# Sheet1.net
KiCad netlist of a schematic drawn in Altium Designer
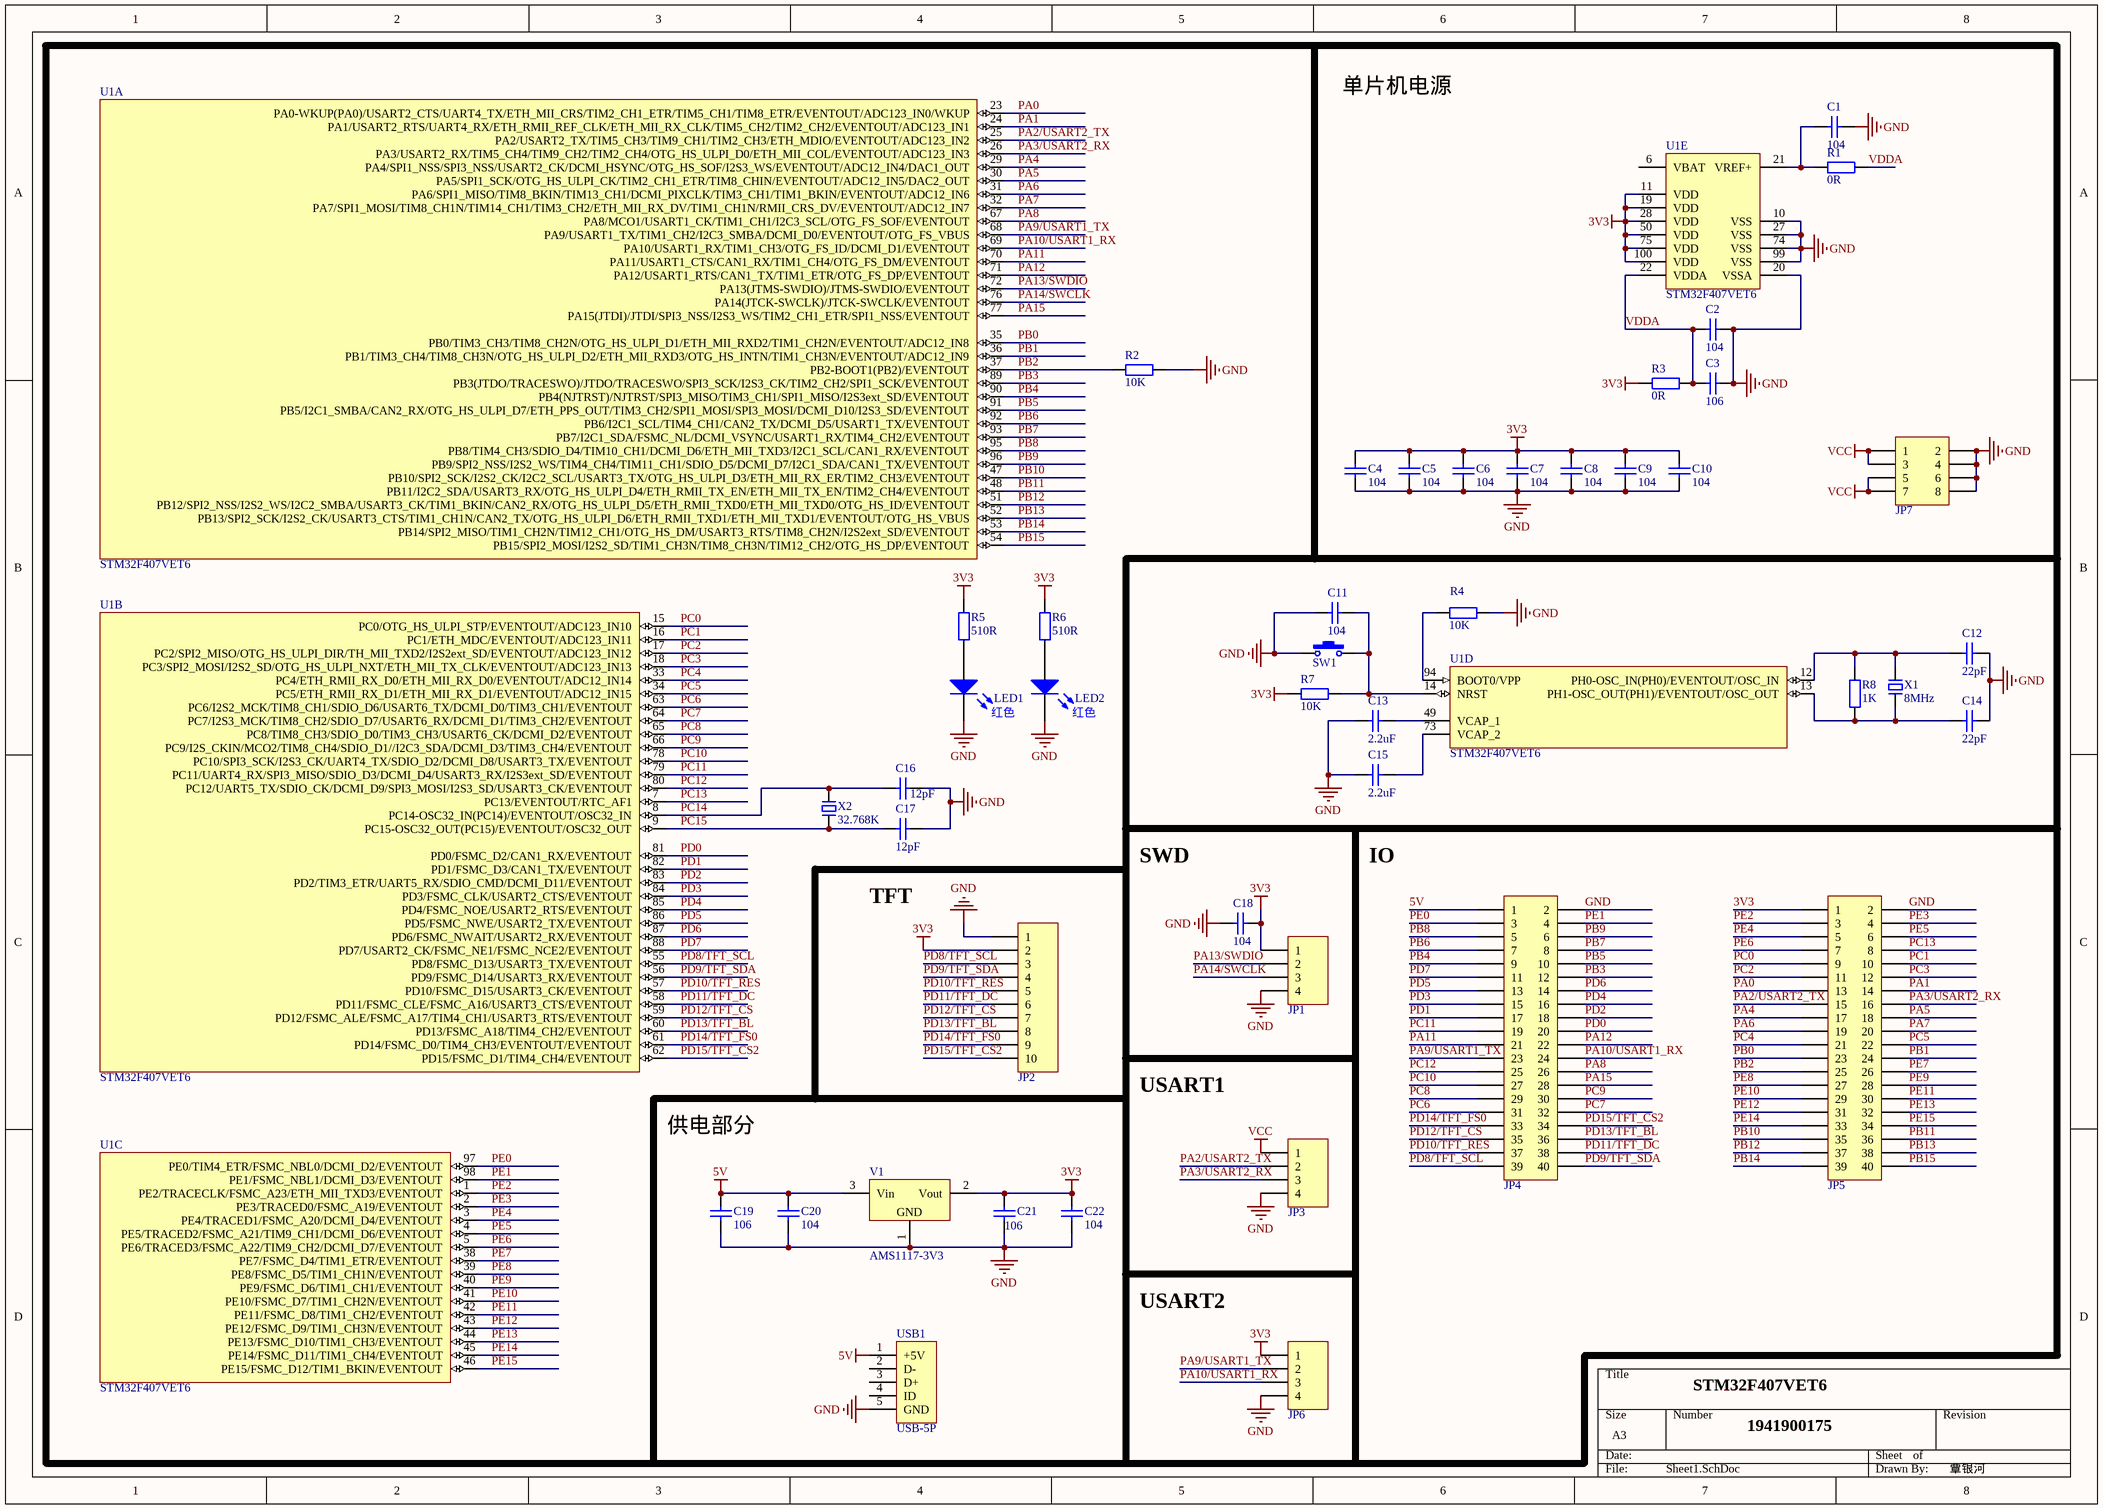
[diagram p0: Sheet1.SchDoc]

(export (version "E")
  (design (tool "Eeschema 10.0.6"))
  (components
    (comp (ref "C1")
      (value "104")
      (footprint "C0603_M")
      (description "贴片电容")
      (libsource (lib "0.1 - 电阻-电容-电感-磁珠-电位器") (part "C"))
    )
    (comp (ref "C2")
      (value "104")
      (footprint "C0603_M")
      (description "贴片电容")
      (libsource (lib "0.1 - 电阻-电容-电感-磁珠-电位器") (part "C"))
    )
    (comp (ref "C3")
      (value "106")
      (footprint "C0603_M")
      (description "贴片电容")
      (libsource (lib "0.1 - 电阻-电容-电感-磁珠-电位器") (part "C"))
    )
    (comp (ref "C4")
      (value "104")
      (footprint "C0603_M")
      (description "贴片电容")
      (libsource (lib "0.1 - 电阻-电容-电感-磁珠-电位器") (part "C"))
    )
    (comp (ref "C5")
      (value "104")
      (footprint "C0603_M")
      (description "贴片电容")
      (libsource (lib "0.1 - 电阻-电容-电感-磁珠-电位器") (part "C"))
    )
    (comp (ref "C6")
      (value "104")
      (footprint "C0603_M")
      (description "贴片电容")
      (libsource (lib "0.1 - 电阻-电容-电感-磁珠-电位器") (part "C"))
    )
    (comp (ref "C7")
      (value "104")
      (footprint "C0603_M")
      (description "贴片电容")
      (libsource (lib "0.1 - 电阻-电容-电感-磁珠-电位器") (part "C"))
    )
    (comp (ref "C8")
      (value "104")
      (footprint "C0603_M")
      (description "贴片电容")
      (libsource (lib "0.1 - 电阻-电容-电感-磁珠-电位器") (part "C"))
    )
    (comp (ref "C9")
      (value "104")
      (footprint "C0603_M")
      (description "贴片电容")
      (libsource (lib "0.1 - 电阻-电容-电感-磁珠-电位器") (part "C"))
    )
    (comp (ref "C10")
      (value "104")
      (footprint "C0603_M")
      (description "贴片电容")
      (libsource (lib "0.1 - 电阻-电容-电感-磁珠-电位器") (part "C"))
    )
    (comp (ref "C11")
      (value "104")
      (footprint "C0603_M")
      (description "贴片电容")
      (libsource (lib "0.1 - 电阻-电容-电感-磁珠-电位器") (part "C"))
    )
    (comp (ref "C12")
      (value "22pF")
      (footprint "C0603_M")
      (description "贴片电容")
      (libsource (lib "0.1 - 电阻-电容-电感-磁珠-电位器") (part "C"))
    )
    (comp (ref "C13")
      (value "2.2uF")
      (footprint "C0603_M")
      (description "贴片电容")
      (libsource (lib "0.1 - 电阻-电容-电感-磁珠-电位器") (part "C"))
    )
    (comp (ref "C14")
      (value "22pF")
      (footprint "C0603_M")
      (description "贴片电容")
      (libsource (lib "0.1 - 电阻-电容-电感-磁珠-电位器") (part "C"))
    )
    (comp (ref "C15")
      (value "2.2uF")
      (footprint "C0603_M")
      (description "贴片电容")
      (libsource (lib "0.1 - 电阻-电容-电感-磁珠-电位器") (part "C"))
    )
    (comp (ref "C16")
      (value "12pF")
      (footprint "C0603_M")
      (description "贴片电容")
      (libsource (lib "0.1 - 电阻-电容-电感-磁珠-电位器") (part "C"))
    )
    (comp (ref "C17")
      (value "12pF")
      (footprint "C0603_M")
      (description "贴片电容")
      (libsource (lib "0.1 - 电阻-电容-电感-磁珠-电位器") (part "C"))
    )
    (comp (ref "C18")
      (value "104")
      (footprint "C0603_M")
      (description "贴片电容")
      (libsource (lib "0.1 - 电阻-电容-电感-磁珠-电位器") (part "C"))
    )
    (comp (ref "C19")
      (value "106")
      (footprint "C0603_M")
      (description "贴片电容")
      (libsource (lib "0.1 - 电阻-电容-电感-磁珠-电位器") (part "C"))
    )
    (comp (ref "C20")
      (value "104")
      (footprint "C0603_M")
      (description "贴片电容")
      (libsource (lib "0.1 - 电阻-电容-电感-磁珠-电位器") (part "C"))
    )
    (comp (ref "C21")
      (value "106")
      (footprint "C0603_M")
      (description "贴片电容")
      (libsource (lib "0.1 - 电阻-电容-电感-磁珠-电位器") (part "C"))
    )
    (comp (ref "C22")
      (value "104")
      (footprint "C0603_M")
      (description "贴片电容")
      (libsource (lib "0.1 - 电阻-电容-电感-磁珠-电位器") (part "C"))
    )
    (comp (ref "LED1")
      (value "LED")
      (footprint "LED0603_R")
      (description "发光二极管")
      (libsource (lib "0.3 - LED发光二极管") (part "LED"))
    )
    (comp (ref "LED2")
      (value "LED")
      (footprint "LED0603_R")
      (description "发光二极管")
      (libsource (lib "0.3 - LED发光二极管") (part "LED"))
    )
    (comp (ref "P1")
      (value "JP7")
      (footprint "HDR2X4")
      (description "Header, 4-Pin, Dual row")
      (fields (field (name "PUBLISHER") "Altium Limited"))
      (libsource (lib "Miscellaneous Connectors") (part "Header 4X2"))
    )
    (comp (ref "P2")
      (value "JP4")
      (footprint "HDR2X20")
      (description "Header, 20-Pin, Dual row")
      (fields (field (name "PUBLISHER") "Altium Limited"))
      (libsource (lib "Miscellaneous Connectors") (part "Header 20X2"))
    )
    (comp (ref "P3")
      (value "JP5")
      (footprint "HDR2X20")
      (description "Header, 20-Pin, Dual row")
      (fields (field (name "PUBLISHER") "Altium Limited"))
      (libsource (lib "Miscellaneous Connectors") (part "Header 20X2"))
    )
    (comp (ref "P4")
      (value "JP2")
      (footprint "HDR1X10")
      (description "Header, 10-Pin")
      (fields (field (name "PUBLISHER") "Altium Limited"))
      (libsource (lib "Miscellaneous Connectors") (part "Header 10"))
    )
    (comp (ref "P5")
      (value "JP1")
      (footprint "HDR1X4")
      (description "Header, 4-Pin")
      (fields (field (name "PUBLISHER") "Altium Limited"))
      (libsource (lib "Miscellaneous Connectors") (part "Header 4"))
    )
    (comp (ref "P6")
      (value "JP3")
      (footprint "HDR1X4")
      (description "Header, 4-Pin")
      (fields (field (name "PUBLISHER") "Altium Limited"))
      (libsource (lib "Miscellaneous Connectors") (part "Header 4"))
    )
    (comp (ref "P7")
      (value "JP6")
      (footprint "HDR1X4")
      (description "Header, 4-Pin")
      (fields (field (name "PUBLISHER") "Altium Limited"))
      (libsource (lib "Miscellaneous Connectors") (part "Header 4"))
    )
    (comp (ref "R1")
      (value "0R")
      (footprint "R0603_M")
      (description "贴片电阻")
      (libsource (lib "0.1 - 电阻-电容-电感-磁珠-电位器") (part "R"))
    )
    (comp (ref "R2")
      (value "10K")
      (footprint "R0603_M")
      (description "贴片电阻")
      (libsource (lib "0.1 - 电阻-电容-电感-磁珠-电位器") (part "R"))
    )
    (comp (ref "R3")
      (value "0R")
      (footprint "R0603_M")
      (description "贴片电阻")
      (libsource (lib "0.1 - 电阻-电容-电感-磁珠-电位器") (part "R"))
    )
    (comp (ref "R4")
      (value "10K")
      (footprint "R0603_M")
      (description "贴片电阻")
      (libsource (lib "0.1 - 电阻-电容-电感-磁珠-电位器") (part "R"))
    )
    (comp (ref "R5")
      (value "510R")
      (footprint "R0603_M")
      (description "贴片电阻")
      (libsource (lib "0.1 - 电阻-电容-电感-磁珠-电位器") (part "R"))
    )
    (comp (ref "R6")
      (value "510R")
      (footprint "R0603_M")
      (description "贴片电阻")
      (libsource (lib "0.1 - 电阻-电容-电感-磁珠-电位器") (part "R"))
    )
    (comp (ref "R7")
      (value "10K")
      (footprint "R0603_M")
      (description "贴片电阻")
      (libsource (lib "0.1 - 电阻-电容-电感-磁珠-电位器") (part "R"))
    )
    (comp (ref "R8")
      (value "1K")
      (footprint "R0603_M")
      (description "贴片电阻")
      (libsource (lib "0.1 - 电阻-电容-电感-磁珠-电位器") (part "R"))
    )
    (comp (ref "SW1")
      (value "3x6x5")
      (footprint "SW SMD-3*6*2.5")
      (description "微动开关")
      (libsource (lib "0.7 - 常用按键-开关-蜂鸣器-电池-测试点") (part "SW-PB"))
    )
    (comp (ref "U1")
      (value "STM32F407VET6")
      (footprint "LQFP100_V")
      (libsource (lib "2.7 - STM32 F4系列单片机") (part "STM32F407VET6"))
    )
    (comp (ref "USB1")
      (value "USB-5P")
      (footprint "USB-MICRO_A")
      (description "微型USB母座")
      (libsource (lib "0.8 - 以太网-音频-Type-C USB插座") (part "USB-5P"))
    )
    (comp (ref "V1")
      (value "AMS1117-3V3")
      (footprint "SOT89_L")
      (description "三端稳压芯片")
      (libsource (lib "1.1 - 电源类芯片") (part "AMS1117_SOT89"))
    )
    (comp (ref "X1")
      (value "8MHz")
      (footprint "OSC 3225-4P")
      (description "2脚无源脚晶振")
      (fields (field (name "版权归属") "源创客"))
      (libsource (lib "10.1 - 保险丝-晶振") (part "XTAL-2P"))
    )
    (comp (ref "X2")
      (value "32.768K")
      (footprint "OSC 6035-2P")
      (description "2脚无源脚晶振")
      (fields (field (name "版权归属") "源创客"))
      (libsource (lib "10.1 - 保险丝-晶振") (part "XTAL-2P"))
    )
  )
  (nets
    (net (code "1") (name "/PA0") (class "Default")
      (node (ref "P3") (pin "13") (pinfunction "13_13") (pintype "passive"))
      (node (ref "U1") (pin "23") (pinfunction "PA0-WKUP(PA0)/USART2_CTS/UART4_TX/ETH_MII_CRS/TIM2_CH1_ETR/TIM5_CH1/TIM8_ETR/EVENTOUT/ADC123_IN0/WKUP_23") (pintype "bidirectional"))
    )
    (net (code "2") (name "/PA1") (class "Default")
      (node (ref "P3") (pin "14") (pinfunction "14_14") (pintype "passive"))
      (node (ref "U1") (pin "24") (pinfunction "PA1/USART2_RTS/UART4_RX/ETH_RMII_REF_CLK/ETH_MII_RX_CLK/TIM5_CH2/TIM2_CH2/EVENTOUT/ADC123_IN1_24") (pintype "bidirectional"))
    )
    (net (code "3") (name "/PA2{slash}USART2_TX") (class "Default")
      (node (ref "P3") (pin "15") (pinfunction "15_15") (pintype "passive"))
      (node (ref "P6") (pin "2") (pinfunction "2_2") (pintype "passive"))
      (node (ref "U1") (pin "25") (pinfunction "PA2/USART2_TX/TIM5_CH3/TIM9_CH1/TIM2_CH3/ETH_MDIO/EVENTOUT/ADC123_IN2_25") (pintype "bidirectional"))
    )
    (net (code "4") (name "/PA3{slash}USART2_RX") (class "Default")
      (node (ref "P3") (pin "16") (pinfunction "16_16") (pintype "passive"))
      (node (ref "P6") (pin "3") (pinfunction "3_3") (pintype "passive"))
      (node (ref "U1") (pin "26") (pinfunction "PA3/USART2_RX/TIM5_CH4/TIM9_CH2/TIM2_CH4/OTG_HS_ULPI_D0/ETH_MII_COL/EVENTOUT/ADC123_IN3_26") (pintype "bidirectional"))
    )
    (net (code "5") (name "/PA4") (class "Default")
      (node (ref "P3") (pin "17") (pinfunction "17_17") (pintype "passive"))
      (node (ref "U1") (pin "29") (pinfunction "PA4/SPI1_NSS/SPI3_NSS/USART2_CK/DCMI_HSYNC/OTG_HS_SOF/I2S3_WS/EVENTOUT/ADC12_IN4/DAC1_OUT_29") (pintype "bidirectional"))
    )
    (net (code "6") (name "/PA5") (class "Default")
      (node (ref "P3") (pin "18") (pinfunction "18_18") (pintype "passive"))
      (node (ref "U1") (pin "30") (pinfunction "PA5/SPI1_SCK/OTG_HS_ULPI_CK/TIM2_CH1_ETR/TIM8_CHIN/EVENTOUT/ADC12_IN5/DAC2_OUT_30") (pintype "bidirectional"))
    )
    (net (code "7") (name "/PA6") (class "Default")
      (node (ref "P3") (pin "19") (pinfunction "19_19") (pintype "passive"))
      (node (ref "U1") (pin "31") (pinfunction "PA6/SPI1_MISO/TIM8_BKIN/TIM13_CH1/DCMI_PIXCLK/TIM3_CH1/TIM1_BKIN/EVENTOUT/ADC12_IN6_31") (pintype "bidirectional"))
    )
    (net (code "8") (name "/PA7") (class "Default")
      (node (ref "P3") (pin "20") (pinfunction "20_20") (pintype "passive"))
      (node (ref "U1") (pin "32") (pinfunction "PA7/SPI1_MOSI/TIM8_CH1N/TIM14_CH1/TIM3_CH2/ETH_MII_RX_DV/TIM1_CH1N/RMII_CRS_DV/EVENTOUT/ADC12_IN7_32") (pintype "bidirectional"))
    )
    (net (code "9") (name "/PA8") (class "Default")
      (node (ref "P2") (pin "26") (pinfunction "26_26") (pintype "passive"))
      (node (ref "U1") (pin "67") (pinfunction "PA8/MCO1/USART1_CK/TIM1_CH1/I2C3_SCL/OTG_FS_SOF/EVENTOUT_67") (pintype "bidirectional"))
    )
    (net (code "10") (name "/PA9{slash}USART1_TX") (class "Default")
      (node (ref "P2") (pin "23") (pinfunction "23_23") (pintype "passive"))
      (node (ref "P7") (pin "2") (pinfunction "2_2") (pintype "passive"))
      (node (ref "U1") (pin "68") (pinfunction "PA9/USART1_TX/TIM1_CH2/I2C3_SMBA/DCMI_D0/EVENTOUT/OTG_FS_VBUS_68") (pintype "bidirectional"))
    )
    (net (code "11") (name "/PA10{slash}USART1_RX") (class "Default")
      (node (ref "P2") (pin "24") (pinfunction "24_24") (pintype "passive"))
      (node (ref "P7") (pin "3") (pinfunction "3_3") (pintype "passive"))
      (node (ref "U1") (pin "69") (pinfunction "PA10/USART1_RX/TIM1_CH3/OTG_FS_ID/DCMI_D1/EVENTOUT_69") (pintype "bidirectional"))
    )
    (net (code "12") (name "/PA11") (class "Default")
      (node (ref "P2") (pin "21") (pinfunction "21_21") (pintype "passive"))
      (node (ref "U1") (pin "70") (pinfunction "PA11/USART1_CTS/CAN1_RX/TIM1_CH4/OTG_FS_DM/EVENTOUT_70") (pintype "bidirectional"))
    )
    (net (code "13") (name "/PA12") (class "Default")
      (node (ref "P2") (pin "22") (pinfunction "22_22") (pintype "passive"))
      (node (ref "U1") (pin "71") (pinfunction "PA12/USART1_RTS/CAN1_TX/TIM1_ETR/OTG_FS_DP/EVENTOUT_71") (pintype "bidirectional"))
    )
    (net (code "14") (name "/PA13{slash}SWDIO") (class "Default")
      (node (ref "P5") (pin "2") (pinfunction "2_2") (pintype "passive"))
      (node (ref "U1") (pin "72") (pinfunction "PA13(JTMS-SWDIO)/JTMS-SWDIO/EVENTOUT_72") (pintype "bidirectional"))
    )
    (net (code "15") (name "/PA14{slash}SWCLK") (class "Default")
      (node (ref "P5") (pin "3") (pinfunction "3_3") (pintype "passive"))
      (node (ref "U1") (pin "76") (pinfunction "PA14(JTCK-SWCLK)/JTCK-SWCLK/EVENTOUT_76") (pintype "bidirectional"))
    )
    (net (code "16") (name "/PA15") (class "Default")
      (node (ref "P2") (pin "28") (pinfunction "28_28") (pintype "passive"))
      (node (ref "U1") (pin "77") (pinfunction "PA15(JTDI)/JTDI/SPI3_NSS/I2S3_WS/TIM2_CH1_ETR/SPI1_NSS/EVENTOUT_77") (pintype "bidirectional"))
    )
    (net (code "17") (name "/PB0") (class "Default")
      (node (ref "P3") (pin "23") (pinfunction "23_23") (pintype "passive"))
      (node (ref "U1") (pin "35") (pinfunction "PB0/TIM3_CH3/TIM8_CH2N/OTG_HS_ULPI_D1/ETH_MII_RXD2/TIM1_CH2N/EVENTOUT/ADC12_IN8_35") (pintype "bidirectional"))
    )
    (net (code "18") (name "/PB1") (class "Default")
      (node (ref "P3") (pin "24") (pinfunction "24_24") (pintype "passive"))
      (node (ref "U1") (pin "36") (pinfunction "PB1/TIM3_CH4/TIM8_CH3N/OTG_HS_ULPI_D2/ETH_MII_RXD3/OTG_HS_INTN/TIM1_CH3N/EVENTOUT/ADC12_IN9_36") (pintype "bidirectional"))
    )
    (net (code "19") (name "/PB2") (class "Default")
      (node (ref "P3") (pin "25") (pinfunction "25_25") (pintype "passive"))
      (node (ref "R2") (pin "1") (pinfunction "1_1") (pintype "passive"))
      (node (ref "U1") (pin "37") (pinfunction "PB2-BOOT1(PB2)/EVENTOUT_37") (pintype "bidirectional"))
    )
    (net (code "20") (name "/PB3") (class "Default")
      (node (ref "P2") (pin "12") (pinfunction "12_12") (pintype "passive"))
      (node (ref "U1") (pin "89") (pinfunction "PB3(JTDO/TRACESWO)/JTDO/TRACESWO/SPI3_SCK/I2S3_CK/TIM2_CH2/SPI1_SCK/EVENTOUT_89") (pintype "bidirectional"))
    )
    (net (code "21") (name "/PB4") (class "Default")
      (node (ref "P2") (pin "9") (pinfunction "9_9") (pintype "passive"))
      (node (ref "U1") (pin "90") (pinfunction "PB4(NJTRST)/NJTRST/SPI3_MISO/TIM3_CH1/SPI1_MISO/I2S3ext_SD/EVENTOUT_90") (pintype "bidirectional"))
    )
    (net (code "22") (name "/PB5") (class "Default")
      (node (ref "P2") (pin "10") (pinfunction "10_10") (pintype "passive"))
      (node (ref "U1") (pin "91") (pinfunction "PB5/I2C1_SMBA/CAN2_RX/OTG_HS_ULPI_D7/ETH_PPS_OUT/TIM3_CH2/SPI1_MOSI/SPI3_MOSI/DCMI_D10/I2S3_SD/EVENTOUT_91") (pintype "bidirectional"))
    )
    (net (code "23") (name "/PB6") (class "Default")
      (node (ref "P2") (pin "7") (pinfunction "7_7") (pintype "passive"))
      (node (ref "U1") (pin "92") (pinfunction "PB6/I2C1_SCL/TIM4_CH1/CAN2_TX/DCMI_D5/USART1_TX/EVENTOUT_92") (pintype "bidirectional"))
    )
    (net (code "24") (name "/PB7") (class "Default")
      (node (ref "P2") (pin "8") (pinfunction "8_8") (pintype "passive"))
      (node (ref "U1") (pin "93") (pinfunction "PB7/I2C1_SDA/FSMC_NL/DCMI_VSYNC/USART1_RX/TIM4_CH2/EVENTOUT_93") (pintype "bidirectional"))
    )
    (net (code "25") (name "/PB8") (class "Default")
      (node (ref "P2") (pin "5") (pinfunction "5_5") (pintype "passive"))
      (node (ref "U1") (pin "95") (pinfunction "PB8/TIM4_CH3/SDIO_D4/TIM10_CH1/DCMI_D6/ETH_MII_TXD3/I2C1_SCL/CAN1_RX/EVENTOUT_95") (pintype "bidirectional"))
    )
    (net (code "26") (name "/PB9") (class "Default")
      (node (ref "P2") (pin "6") (pinfunction "6_6") (pintype "passive"))
      (node (ref "U1") (pin "96") (pinfunction "PB9/SPI2_NSS/I2S2_WS/TIM4_CH4/TIM11_CH1/SDIO_D5/DCMI_D7/I2C1_SDA/CAN1_TX/EVENTOUT_96") (pintype "bidirectional"))
    )
    (net (code "27") (name "/PB10") (class "Default")
      (node (ref "P3") (pin "35") (pinfunction "35_35") (pintype "passive"))
      (node (ref "U1") (pin "47") (pinfunction "PB10/SPI2_SCK/I2S2_CK/I2C2_SCL/USART3_TX/OTG_HS_ULPI_D3/ETH_MII_RX_ER/TIM2_CH3/EVENTOUT_47") (pintype "bidirectional"))
    )
    (net (code "28") (name "/PB11") (class "Default")
      (node (ref "P3") (pin "36") (pinfunction "36_36") (pintype "passive"))
      (node (ref "U1") (pin "48") (pinfunction "PB11/I2C2_SDA/USART3_RX/OTG_HS_ULPI_D4/ETH_RMII_TX_EN/ETH_MII_TX_EN/TIM2_CH4/EVENTOUT_48") (pintype "bidirectional"))
    )
    (net (code "29") (name "/PB12") (class "Default")
      (node (ref "P3") (pin "37") (pinfunction "37_37") (pintype "passive"))
      (node (ref "U1") (pin "51") (pinfunction "PB12/SPI2_NSS/I2S2_WS/I2C2_SMBA/USART3_CK/TIM1_BKIN/CAN2_RX/OTG_HS_ULPI_D5/ETH_RMII_TXD0/ETH_MII_TXD0/OTG_HS_ID/EVENTOUT_51") (pintype "bidirectional"))
    )
    (net (code "30") (name "/PB13") (class "Default")
      (node (ref "P3") (pin "38") (pinfunction "38_38") (pintype "passive"))
      (node (ref "U1") (pin "52") (pinfunction "PB13/SPI2_SCK/I2S2_CK/USART3_CTS/TIM1_CH1N/CAN2_TX/OTG_HS_ULPI_D6/ETH_RMII_TXD1/ETH_MII_TXD1/EVENTOUT/OTG_HS_VBUS_52") (pintype "bidirectional"))
    )
    (net (code "31") (name "/PB14") (class "Default")
      (node (ref "P3") (pin "39") (pinfunction "39_39") (pintype "passive"))
      (node (ref "U1") (pin "53") (pinfunction "PB14/SPI2_MISO/TIM1_CH2N/TIM12_CH1/OTG_HS_DM/USART3_RTS/TIM8_CH2N/I2S2ext_SD/EVENTOUT_53") (pintype "bidirectional"))
    )
    (net (code "32") (name "/PB15") (class "Default")
      (node (ref "P3") (pin "40") (pinfunction "40_40") (pintype "passive"))
      (node (ref "U1") (pin "54") (pinfunction "PB15/SPI2_MOSI/I2S2_SD/TIM1_CH3N/TIM8_CH3N/TIM12_CH2/OTG_HS_DP/EVENTOUT_54") (pintype "bidirectional"))
    )
    (net (code "33") (name "/PC0") (class "Default")
      (node (ref "P3") (pin "9") (pinfunction "9_9") (pintype "passive"))
      (node (ref "U1") (pin "15") (pinfunction "PC0/OTG_HS_ULPI_STP/EVENTOUT/ADC123_IN10_15") (pintype "bidirectional"))
    )
    (net (code "34") (name "/PC1") (class "Default")
      (node (ref "P3") (pin "10") (pinfunction "10_10") (pintype "passive"))
      (node (ref "U1") (pin "16") (pinfunction "PC1/ETH_MDC/EVENTOUT/ADC123_IN11_16") (pintype "bidirectional"))
    )
    (net (code "35") (name "/PC2") (class "Default")
      (node (ref "P3") (pin "11") (pinfunction "11_11") (pintype "passive"))
      (node (ref "U1") (pin "17") (pinfunction "PC2/SPI2_MISO/OTG_HS_ULPI_DIR/TH_MII_TXD2/I2S2ext_SD/EVENTOUT/ADC123_IN12_17") (pintype "bidirectional"))
    )
    (net (code "36") (name "/PC3") (class "Default")
      (node (ref "P3") (pin "12") (pinfunction "12_12") (pintype "passive"))
      (node (ref "U1") (pin "18") (pinfunction "PC3/SPI2_MOSI/I2S2_SD/OTG_HS_ULPI_NXT/ETH_MII_TX_CLK/EVENTOUT/ADC123_IN13_18") (pintype "bidirectional"))
    )
    (net (code "37") (name "/PC4") (class "Default")
      (node (ref "P3") (pin "21") (pinfunction "21_21") (pintype "passive"))
      (node (ref "U1") (pin "33") (pinfunction "PC4/ETH_RMII_RX_D0/ETH_MII_RX_D0/EVENTOUT/ADC12_IN14_33") (pintype "bidirectional"))
    )
    (net (code "38") (name "/PC5") (class "Default")
      (node (ref "P3") (pin "22") (pinfunction "22_22") (pintype "passive"))
      (node (ref "U1") (pin "34") (pinfunction "PC5/ETH_RMII_RX_D1/ETH_MII_RX_D1/EVENTOUT/ADC12_IN15_34") (pintype "bidirectional"))
    )
    (net (code "39") (name "/PC6") (class "Default")
      (node (ref "P2") (pin "31") (pinfunction "31_31") (pintype "passive"))
      (node (ref "U1") (pin "63") (pinfunction "PC6/I2S2_MCK/TIM8_CH1/SDIO_D6/USART6_TX/DCMI_D0/TIM3_CH1/EVENTOUT_63") (pintype "bidirectional"))
    )
    (net (code "40") (name "/PC7") (class "Default")
      (node (ref "P2") (pin "32") (pinfunction "32_32") (pintype "passive"))
      (node (ref "U1") (pin "64") (pinfunction "PC7/I2S3_MCK/TIM8_CH2/SDIO_D7/USART6_RX/DCMI_D1/TIM3_CH2/EVENTOUT_64") (pintype "bidirectional"))
    )
    (net (code "41") (name "/PC8") (class "Default")
      (node (ref "P2") (pin "29") (pinfunction "29_29") (pintype "passive"))
      (node (ref "U1") (pin "65") (pinfunction "PC8/TIM8_CH3/SDIO_D0/TIM3_CH3/USART6_CK/DCMI_D2/EVENTOUT_65") (pintype "bidirectional"))
    )
    (net (code "42") (name "/PC9") (class "Default")
      (node (ref "P2") (pin "30") (pinfunction "30_30") (pintype "passive"))
      (node (ref "U1") (pin "66") (pinfunction "PC9/I2S_CKIN/MCO2/TIM8_CH4/SDIO_D1//I2C3_SDA/DCMI_D3/TIM3_CH4/EVENTOUT_66") (pintype "bidirectional"))
    )
    (net (code "43") (name "/PC10") (class "Default")
      (node (ref "P2") (pin "27") (pinfunction "27_27") (pintype "passive"))
      (node (ref "U1") (pin "78") (pinfunction "PC10/SPI3_SCK/I2S3_CK/UART4_TX/SDIO_D2/DCMI_D8/USART3_TX/EVENTOUT_78") (pintype "bidirectional"))
    )
    (net (code "44") (name "/PC11") (class "Default")
      (node (ref "P2") (pin "19") (pinfunction "19_19") (pintype "passive"))
      (node (ref "U1") (pin "79") (pinfunction "PC11/UART4_RX/SPI3_MISO/SDIO_D3/DCMI_D4/USART3_RX/I2S3ext_SD/EVENTOUT_79") (pintype "bidirectional"))
    )
    (net (code "45") (name "/PC12") (class "Default")
      (node (ref "P2") (pin "25") (pinfunction "25_25") (pintype "passive"))
      (node (ref "U1") (pin "80") (pinfunction "PC12/UART5_TX/SDIO_CK/DCMI_D9/SPI3_MOSI/I2S3_SD/USART3_CK/EVENTOUT_80") (pintype "bidirectional"))
    )
    (net (code "46") (name "/PC13") (class "Default")
      (node (ref "P3") (pin "8") (pinfunction "8_8") (pintype "passive"))
      (node (ref "U1") (pin "7") (pinfunction "PC13/EVENTOUT/RTC_AF1_7") (pintype "bidirectional"))
    )
    (net (code "47") (name "/PC14") (class "Default")
      (node (ref "C16") (pin "2") (pinfunction "2_2") (pintype "passive"))
      (node (ref "U1") (pin "8") (pinfunction "PC14-OSC32_IN(PC14)/EVENTOUT/OSC32_IN_8") (pintype "bidirectional"))
      (node (ref "X2") (pin "2") (pinfunction "2_2") (pintype "passive"))
    )
    (net (code "48") (name "/PC15") (class "Default")
      (node (ref "C17") (pin "2") (pinfunction "2_2") (pintype "passive"))
      (node (ref "U1") (pin "9") (pinfunction "PC15-OSC32_OUT(PC15)/EVENTOUT/OSC32_OUT_9") (pintype "bidirectional"))
      (node (ref "X2") (pin "1") (pinfunction "1_1") (pintype "passive"))
    )
    (net (code "49") (name "/PD0") (class "Default")
      (node (ref "P2") (pin "20") (pinfunction "20_20") (pintype "passive"))
      (node (ref "U1") (pin "81") (pinfunction "PD0/FSMC_D2/CAN1_RX/EVENTOUT_81") (pintype "bidirectional"))
    )
    (net (code "50") (name "/PD1") (class "Default")
      (node (ref "P2") (pin "17") (pinfunction "17_17") (pintype "passive"))
      (node (ref "U1") (pin "82") (pinfunction "PD1/FSMC_D3/CAN1_TX/EVENTOUT_82") (pintype "bidirectional"))
    )
    (net (code "51") (name "/PD2") (class "Default")
      (node (ref "P2") (pin "18") (pinfunction "18_18") (pintype "passive"))
      (node (ref "U1") (pin "83") (pinfunction "PD2/TIM3_ETR/UART5_RX/SDIO_CMD/DCMI_D11/EVENTOUT_83") (pintype "bidirectional"))
    )
    (net (code "52") (name "/PD3") (class "Default")
      (node (ref "P2") (pin "15") (pinfunction "15_15") (pintype "passive"))
      (node (ref "U1") (pin "84") (pinfunction "PD3/FSMC_CLK/USART2_CTS/EVENTOUT_84") (pintype "bidirectional"))
    )
    (net (code "53") (name "/PD4") (class "Default")
      (node (ref "P2") (pin "16") (pinfunction "16_16") (pintype "passive"))
      (node (ref "U1") (pin "85") (pinfunction "PD4/FSMC_NOE/USART2_RTS/EVENTOUT_85") (pintype "bidirectional"))
    )
    (net (code "54") (name "/PD5") (class "Default")
      (node (ref "P2") (pin "13") (pinfunction "13_13") (pintype "passive"))
      (node (ref "U1") (pin "86") (pinfunction "PD5/FSMC_NWE/USART2_TX/EVENTOUT_86") (pintype "bidirectional"))
    )
    (net (code "55") (name "/PD6") (class "Default")
      (node (ref "P2") (pin "14") (pinfunction "14_14") (pintype "passive"))
      (node (ref "U1") (pin "87") (pinfunction "PD6/FSMC_NWAIT/USART2_RX/EVENTOUT_87") (pintype "bidirectional"))
    )
    (net (code "56") (name "/PD7") (class "Default")
      (node (ref "P2") (pin "11") (pinfunction "11_11") (pintype "passive"))
      (node (ref "U1") (pin "88") (pinfunction "PD7/USART2_CK/FSMC_NE1/FSMC_NCE2/EVENTOUT_88") (pintype "bidirectional"))
    )
    (net (code "57") (name "/PD8{slash}TFT_SCL") (class "Default")
      (node (ref "P2") (pin "39") (pinfunction "39_39") (pintype "passive"))
      (node (ref "P4") (pin "3") (pinfunction "3_3") (pintype "passive"))
      (node (ref "U1") (pin "55") (pinfunction "PD8/FSMC_D13/USART3_TX/EVENTOUT_55") (pintype "bidirectional"))
    )
    (net (code "58") (name "/PD9{slash}TFT_SDA") (class "Default")
      (node (ref "P2") (pin "40") (pinfunction "40_40") (pintype "passive"))
      (node (ref "P4") (pin "4") (pinfunction "4_4") (pintype "passive"))
      (node (ref "U1") (pin "56") (pinfunction "PD9/FSMC_D14/USART3_RX/EVENTOUT_56") (pintype "bidirectional"))
    )
    (net (code "59") (name "/PD10{slash}TFT_RES") (class "Default")
      (node (ref "P2") (pin "37") (pinfunction "37_37") (pintype "passive"))
      (node (ref "P4") (pin "5") (pinfunction "5_5") (pintype "passive"))
      (node (ref "U1") (pin "57") (pinfunction "PD10/FSMC_D15/USART3_CK/EVENTOUT_57") (pintype "bidirectional"))
    )
    (net (code "60") (name "/PD11{slash}TFT_DC") (class "Default")
      (node (ref "P2") (pin "38") (pinfunction "38_38") (pintype "passive"))
      (node (ref "P4") (pin "6") (pinfunction "6_6") (pintype "passive"))
      (node (ref "U1") (pin "58") (pinfunction "PD11/FSMC_CLE/FSMC_A16/USART3_CTS/EVENTOUT_58") (pintype "bidirectional"))
    )
    (net (code "61") (name "/PD12{slash}TFT_CS") (class "Default")
      (node (ref "P2") (pin "35") (pinfunction "35_35") (pintype "passive"))
      (node (ref "P4") (pin "7") (pinfunction "7_7") (pintype "passive"))
      (node (ref "U1") (pin "59") (pinfunction "PD12/FSMC_ALE/FSMC_A17/TIM4_CH1/USART3_RTS/EVENTOUT_59") (pintype "bidirectional"))
    )
    (net (code "62") (name "/PD13{slash}TFT_BL") (class "Default")
      (node (ref "P2") (pin "36") (pinfunction "36_36") (pintype "passive"))
      (node (ref "P4") (pin "8") (pinfunction "8_8") (pintype "passive"))
      (node (ref "U1") (pin "60") (pinfunction "PD13/FSMC_A18/TIM4_CH2/EVENTOUT_60") (pintype "bidirectional"))
    )
    (net (code "63") (name "/PD14{slash}TFT_FS0") (class "Default")
      (node (ref "P2") (pin "33") (pinfunction "33_33") (pintype "passive"))
      (node (ref "P4") (pin "9") (pinfunction "9_9") (pintype "passive"))
      (node (ref "U1") (pin "61") (pinfunction "PD14/FSMC_D0/TIM4_CH3/EVENTOUT/EVENTOUT_61") (pintype "bidirectional"))
    )
    (net (code "64") (name "/PD15{slash}TFT_CS2") (class "Default")
      (node (ref "P2") (pin "34") (pinfunction "34_34") (pintype "passive"))
      (node (ref "P4") (pin "10") (pinfunction "10_10") (pintype "passive"))
      (node (ref "U1") (pin "62") (pinfunction "PD15/FSMC_D1/TIM4_CH4/EVENTOUT_62") (pintype "bidirectional"))
    )
    (net (code "65") (name "/PE0") (class "Default")
      (node (ref "P2") (pin "3") (pinfunction "3_3") (pintype "passive"))
      (node (ref "U1") (pin "97") (pinfunction "PE0/TIM4_ETR/FSMC_NBL0/DCMI_D2/EVENTOUT_97") (pintype "bidirectional"))
    )
    (net (code "66") (name "/PE1") (class "Default")
      (node (ref "P2") (pin "4") (pinfunction "4_4") (pintype "passive"))
      (node (ref "U1") (pin "98") (pinfunction "PE1/FSMC_NBL1/DCMI_D3/EVENTOUT_98") (pintype "bidirectional"))
    )
    (net (code "67") (name "/PE2") (class "Default")
      (node (ref "P3") (pin "3") (pinfunction "3_3") (pintype "passive"))
      (node (ref "U1") (pin "1") (pinfunction "PE2/TRACECLK/FSMC_A23/ETH_MII_TXD3/EVENTOUT_1") (pintype "bidirectional"))
    )
    (net (code "68") (name "/PE3") (class "Default")
      (node (ref "P3") (pin "4") (pinfunction "4_4") (pintype "passive"))
      (node (ref "U1") (pin "2") (pinfunction "PE3/TRACED0/FSMC_A19/EVENTOUT_2") (pintype "bidirectional"))
    )
    (net (code "69") (name "/PE4") (class "Default")
      (node (ref "P3") (pin "5") (pinfunction "5_5") (pintype "passive"))
      (node (ref "U1") (pin "3") (pinfunction "PE4/TRACED1/FSMC_A20/DCMI_D4/EVENTOUT_3") (pintype "bidirectional"))
    )
    (net (code "70") (name "/PE5") (class "Default")
      (node (ref "P3") (pin "6") (pinfunction "6_6") (pintype "passive"))
      (node (ref "U1") (pin "4") (pinfunction "PE5/TRACED2/FSMC_A21/TIM9_CH1/DCMI_D6/EVENTOUT_4") (pintype "bidirectional"))
    )
    (net (code "71") (name "/PE6") (class "Default")
      (node (ref "P3") (pin "7") (pinfunction "7_7") (pintype "passive"))
      (node (ref "U1") (pin "5") (pinfunction "PE6/TRACED3/FSMC_A22/TIM9_CH2/DCMI_D7/EVENTOUT_5") (pintype "bidirectional"))
    )
    (net (code "72") (name "/PE7") (class "Default")
      (node (ref "P3") (pin "26") (pinfunction "26_26") (pintype "passive"))
      (node (ref "U1") (pin "38") (pinfunction "PE7/FSMC_D4/TIM1_ETR/EVENTOUT_38") (pintype "bidirectional"))
    )
    (net (code "73") (name "/PE8") (class "Default")
      (node (ref "P3") (pin "27") (pinfunction "27_27") (pintype "passive"))
      (node (ref "U1") (pin "39") (pinfunction "PE8/FSMC_D5/TIM1_CH1N/EVENTOUT_39") (pintype "bidirectional"))
    )
    (net (code "74") (name "/PE9") (class "Default")
      (node (ref "P3") (pin "28") (pinfunction "28_28") (pintype "passive"))
      (node (ref "U1") (pin "40") (pinfunction "PE9/FSMC_D6/TIM1_CH1/EVENTOUT_40") (pintype "bidirectional"))
    )
    (net (code "75") (name "/PE10") (class "Default")
      (node (ref "P3") (pin "29") (pinfunction "29_29") (pintype "passive"))
      (node (ref "U1") (pin "41") (pinfunction "PE10/FSMC_D7/TIM1_CH2N/EVENTOUT_41") (pintype "bidirectional"))
    )
    (net (code "76") (name "/PE11") (class "Default")
      (node (ref "P3") (pin "30") (pinfunction "30_30") (pintype "passive"))
      (node (ref "U1") (pin "42") (pinfunction "PE11/FSMC_D8/TIM1_CH2/EVENTOUT_42") (pintype "bidirectional"))
    )
    (net (code "77") (name "/PE12") (class "Default")
      (node (ref "P3") (pin "31") (pinfunction "31_31") (pintype "passive"))
      (node (ref "U1") (pin "43") (pinfunction "PE12/FSMC_D9/TIM1_CH3N/EVENTOUT_43") (pintype "bidirectional"))
    )
    (net (code "78") (name "/PE13") (class "Default")
      (node (ref "P3") (pin "32") (pinfunction "32_32") (pintype "passive"))
      (node (ref "U1") (pin "44") (pinfunction "PE13/FSMC_D10/TIM1_CH3/EVENTOUT_44") (pintype "bidirectional"))
    )
    (net (code "79") (name "/PE14") (class "Default")
      (node (ref "P3") (pin "33") (pinfunction "33_33") (pintype "passive"))
      (node (ref "U1") (pin "45") (pinfunction "PE14/FSMC_D11/TIM1_CH4/EVENTOUT_45") (pintype "bidirectional"))
    )
    (net (code "80") (name "/PE15") (class "Default")
      (node (ref "P3") (pin "34") (pinfunction "34_34") (pintype "passive"))
      (node (ref "U1") (pin "46") (pinfunction "PE15/FSMC_D12/TIM1_BKIN/EVENTOUT_46") (pintype "bidirectional"))
    )
    (net (code "81") (name "/VDDA") (class "Default")
      (node (ref "C2") (pin "2") (pinfunction "2_2") (pintype "passive"))
      (node (ref "C3") (pin "2") (pinfunction "2_2") (pintype "passive"))
      (node (ref "R1") (pin "2") (pinfunction "2_2") (pintype "passive"))
      (node (ref "R3") (pin "2") (pinfunction "2_2") (pintype "passive"))
      (node (ref "U1") (pin "22") (pinfunction "VDDA_22") (pintype "power_in"))
    )
    (net (code "82") (name "3V3") (class "Default")
      (node (ref "C10") (pin "2") (pinfunction "2_2") (pintype "passive"))
      (node (ref "C18") (pin "2") (pinfunction "2_2") (pintype "passive"))
      (node (ref "C21") (pin "2") (pinfunction "2_2") (pintype "passive"))
      (node (ref "C22") (pin "2") (pinfunction "2_2") (pintype "passive"))
      (node (ref "C4") (pin "2") (pinfunction "2_2") (pintype "passive"))
      (node (ref "C5") (pin "2") (pinfunction "2_2") (pintype "passive"))
      (node (ref "C6") (pin "2") (pinfunction "2_2") (pintype "passive"))
      (node (ref "C7") (pin "2") (pinfunction "2_2") (pintype "passive"))
      (node (ref "C8") (pin "2") (pinfunction "2_2") (pintype "passive"))
      (node (ref "C9") (pin "2") (pinfunction "2_2") (pintype "passive"))
      (node (ref "P3") (pin "1") (pinfunction "1_1") (pintype "passive"))
      (node (ref "P4") (pin "2") (pinfunction "2_2") (pintype "passive"))
      (node (ref "P5") (pin "1") (pinfunction "1_1") (pintype "passive"))
      (node (ref "P7") (pin "1") (pinfunction "1_1") (pintype "passive"))
      (node (ref "R3") (pin "1") (pinfunction "1_1") (pintype "passive"))
      (node (ref "R5") (pin "2") (pinfunction "2_2") (pintype "passive"))
      (node (ref "R6") (pin "2") (pinfunction "2_2") (pintype "passive"))
      (node (ref "R7") (pin "1") (pinfunction "1_1") (pintype "passive"))
      (node (ref "U1") (pin "100") (pinfunction "VDD_100") (pintype "power_in"))
      (node (ref "U1") (pin "11") (pinfunction "VDD_11") (pintype "power_in"))
      (node (ref "U1") (pin "19") (pinfunction "VDD_19") (pintype "power_in"))
      (node (ref "U1") (pin "28") (pinfunction "VDD_28") (pintype "power_in"))
      (node (ref "U1") (pin "50") (pinfunction "VDD_50") (pintype "power_in"))
      (node (ref "U1") (pin "75") (pinfunction "VDD_75") (pintype "power_in"))
      (node (ref "V1") (pin "2") (pinfunction "Vout_2") (pintype "passive"))
    )
    (net (code "83") (name "5V") (class "Default")
      (node (ref "C19") (pin "2") (pinfunction "2_2") (pintype "passive"))
      (node (ref "C20") (pin "2") (pinfunction "2_2") (pintype "passive"))
      (node (ref "P2") (pin "1") (pinfunction "1_1") (pintype "passive"))
      (node (ref "USB1") (pin "1") (pinfunction "+5V_1") (pintype "passive"))
      (node (ref "V1") (pin "3") (pinfunction "Vin_3") (pintype "passive"))
    )
    (net (code "84") (name "GND") (class "Default")
      (node (ref "C1") (pin "2") (pinfunction "2_2") (pintype "passive"))
      (node (ref "C10") (pin "1") (pinfunction "1_1") (pintype "passive"))
      (node (ref "C11") (pin "2") (pinfunction "2_2") (pintype "passive"))
      (node (ref "C12") (pin "1") (pinfunction "1_1") (pintype "passive"))
      (node (ref "C13") (pin "2") (pinfunction "2_2") (pintype "passive"))
      (node (ref "C14") (pin "1") (pinfunction "1_1") (pintype "passive"))
      (node (ref "C15") (pin "2") (pinfunction "2_2") (pintype "passive"))
      (node (ref "C16") (pin "1") (pinfunction "1_1") (pintype "passive"))
      (node (ref "C17") (pin "1") (pinfunction "1_1") (pintype "passive"))
      (node (ref "C18") (pin "1") (pinfunction "1_1") (pintype "passive"))
      (node (ref "C19") (pin "1") (pinfunction "1_1") (pintype "passive"))
      (node (ref "C2") (pin "1") (pinfunction "1_1") (pintype "passive"))
      (node (ref "C20") (pin "1") (pinfunction "1_1") (pintype "passive"))
      (node (ref "C21") (pin "1") (pinfunction "1_1") (pintype "passive"))
      (node (ref "C22") (pin "1") (pinfunction "1_1") (pintype "passive"))
      (node (ref "C3") (pin "1") (pinfunction "1_1") (pintype "passive"))
      (node (ref "C4") (pin "1") (pinfunction "1_1") (pintype "passive"))
      (node (ref "C5") (pin "1") (pinfunction "1_1") (pintype "passive"))
      (node (ref "C6") (pin "1") (pinfunction "1_1") (pintype "passive"))
      (node (ref "C7") (pin "1") (pinfunction "1_1") (pintype "passive"))
      (node (ref "C8") (pin "1") (pinfunction "1_1") (pintype "passive"))
      (node (ref "C9") (pin "1") (pinfunction "1_1") (pintype "passive"))
      (node (ref "LED1") (pin "2") (pinfunction "K_2") (pintype "passive"))
      (node (ref "LED2") (pin "2") (pinfunction "K_2") (pintype "passive"))
      (node (ref "P1") (pin "2") (pinfunction "2_2") (pintype "passive"))
      (node (ref "P1") (pin "4") (pinfunction "4_4") (pintype "passive"))
      (node (ref "P1") (pin "6") (pinfunction "6_6") (pintype "passive"))
      (node (ref "P1") (pin "8") (pinfunction "8_8") (pintype "passive"))
      (node (ref "P2") (pin "2") (pinfunction "2_2") (pintype "passive"))
      (node (ref "P3") (pin "2") (pinfunction "2_2") (pintype "passive"))
      (node (ref "P4") (pin "1") (pinfunction "1_1") (pintype "passive"))
      (node (ref "P5") (pin "4") (pinfunction "4_4") (pintype "passive"))
      (node (ref "P6") (pin "4") (pinfunction "4_4") (pintype "passive"))
      (node (ref "P7") (pin "4") (pinfunction "4_4") (pintype "passive"))
      (node (ref "R2") (pin "2") (pinfunction "2_2") (pintype "passive"))
      (node (ref "R4") (pin "1") (pinfunction "1_1") (pintype "passive"))
      (node (ref "SW1") (pin "1") (pinfunction "1_1") (pintype "passive"))
      (node (ref "U1") (pin "10") (pinfunction "VSS_10") (pintype "power_in"))
      (node (ref "U1") (pin "20") (pinfunction "VSSA_20") (pintype "power_in"))
      (node (ref "U1") (pin "27") (pinfunction "VSS_27") (pintype "power_in"))
      (node (ref "U1") (pin "74") (pinfunction "VSS_74") (pintype "power_in"))
      (node (ref "U1") (pin "99") (pinfunction "VSS_99") (pintype "power_in"))
      (node (ref "USB1") (pin "5") (pinfunction "GND_5") (pintype "passive"))
      (node (ref "V1") (pin "1") (pinfunction "GND_1") (pintype "passive"))
    )
    (net (code "85") (name "Net-(LED1-A)") (class "Default")
      (node (ref "LED1") (pin "1") (pinfunction "A_1") (pintype "passive"))
      (node (ref "R5") (pin "1") (pinfunction "1_1") (pintype "passive"))
    )
    (net (code "86") (name "Net-(LED2-A)") (class "Default")
      (node (ref "LED2") (pin "1") (pinfunction "A_1") (pintype "passive"))
      (node (ref "R6") (pin "1") (pinfunction "1_1") (pintype "passive"))
    )
    (net (code "87") (name "Net-(U1D-BOOT0{slash}VPP)") (class "Default")
      (node (ref "R4") (pin "2") (pinfunction "2_2") (pintype "passive"))
      (node (ref "U1") (pin "94") (pinfunction "BOOT0/VPP_94") (pintype "input"))
    )
    (net (code "88") (name "Net-(U1D-NRST)") (class "Default")
      (node (ref "C11") (pin "1") (pinfunction "1_1") (pintype "passive"))
      (node (ref "R7") (pin "2") (pinfunction "2_2") (pintype "passive"))
      (node (ref "SW1") (pin "2") (pinfunction "2_2") (pintype "passive"))
      (node (ref "U1") (pin "14") (pinfunction "NRST_14") (pintype "bidirectional"))
    )
    (net (code "89") (name "Net-(U1D-PH0-OSC_IN(PH0){slash}EVENTOUT{slash}OSC_IN)") (class "Default")
      (node (ref "C12") (pin "2") (pinfunction "2_2") (pintype "passive"))
      (node (ref "R8") (pin "2") (pinfunction "2_2") (pintype "passive"))
      (node (ref "U1") (pin "12") (pinfunction "PH0-OSC_IN(PH0)/EVENTOUT/OSC_IN_12") (pintype "bidirectional"))
      (node (ref "X1") (pin "2") (pinfunction "2_2") (pintype "passive"))
    )
    (net (code "90") (name "Net-(U1D-PH1-OSC_OUT(PH1){slash}EVENTOUT{slash}OSC_OUT)") (class "Default")
      (node (ref "C14") (pin "2") (pinfunction "2_2") (pintype "passive"))
      (node (ref "R8") (pin "1") (pinfunction "1_1") (pintype "passive"))
      (node (ref "U1") (pin "13") (pinfunction "PH1-OSC_OUT(PH1)/EVENTOUT/OSC_OUT_13") (pintype "bidirectional"))
      (node (ref "X1") (pin "1") (pinfunction "1_1") (pintype "passive"))
    )
    (net (code "91") (name "Net-(U1D-VCAP_1)") (class "Default")
      (node (ref "C13") (pin "1") (pinfunction "1_1") (pintype "passive"))
      (node (ref "U1") (pin "49") (pinfunction "VCAP_1_49") (pintype "power_in"))
    )
    (net (code "92") (name "Net-(U1D-VCAP_2)") (class "Default")
      (node (ref "C15") (pin "1") (pinfunction "1_1") (pintype "passive"))
      (node (ref "U1") (pin "73") (pinfunction "VCAP_2_73") (pintype "power_in"))
    )
    (net (code "93") (name "Net-(U1E-VREF+)") (class "Default")
      (node (ref "C1") (pin "1") (pinfunction "1_1") (pintype "passive"))
      (node (ref "R1") (pin "1") (pinfunction "1_1") (pintype "passive"))
      (node (ref "U1") (pin "21") (pinfunction "VREF+_21") (pintype "power_in"))
    )
    (net (code "94") (name "VCC") (class "Default")
      (node (ref "P1") (pin "1") (pinfunction "1_1") (pintype "passive"))
      (node (ref "P1") (pin "3") (pinfunction "3_3") (pintype "passive"))
      (node (ref "P1") (pin "5") (pinfunction "5_5") (pintype "passive"))
      (node (ref "P1") (pin "7") (pinfunction "7_7") (pintype "passive"))
      (node (ref "P6") (pin "1") (pinfunction "1_1") (pintype "passive"))
    )
    (net (code "95") (name "unconnected-(U1E-VBAT-Pad6)") (class "Default")
      (node (ref "U1") (pin "6") (pinfunction "VBAT_6") (pintype "power_in"))
    )
    (net (code "96") (name "unconnected-(USB1-D+-Pad3)") (class "Default")
      (node (ref "USB1") (pin "3") (pinfunction "D+_3") (pintype "passive"))
    )
    (net (code "97") (name "unconnected-(USB1-D--Pad2)") (class "Default")
      (node (ref "USB1") (pin "2") (pinfunction "D-_2") (pintype "passive"))
    )
    (net (code "98") (name "unconnected-(USB1-ID-Pad4)") (class "Default")
      (node (ref "USB1") (pin "4") (pinfunction "ID_4") (pintype "passive"))
    )
  )
)
